# MAGHUG.net
KiCad netlist of a schematic drawn in EAGLE
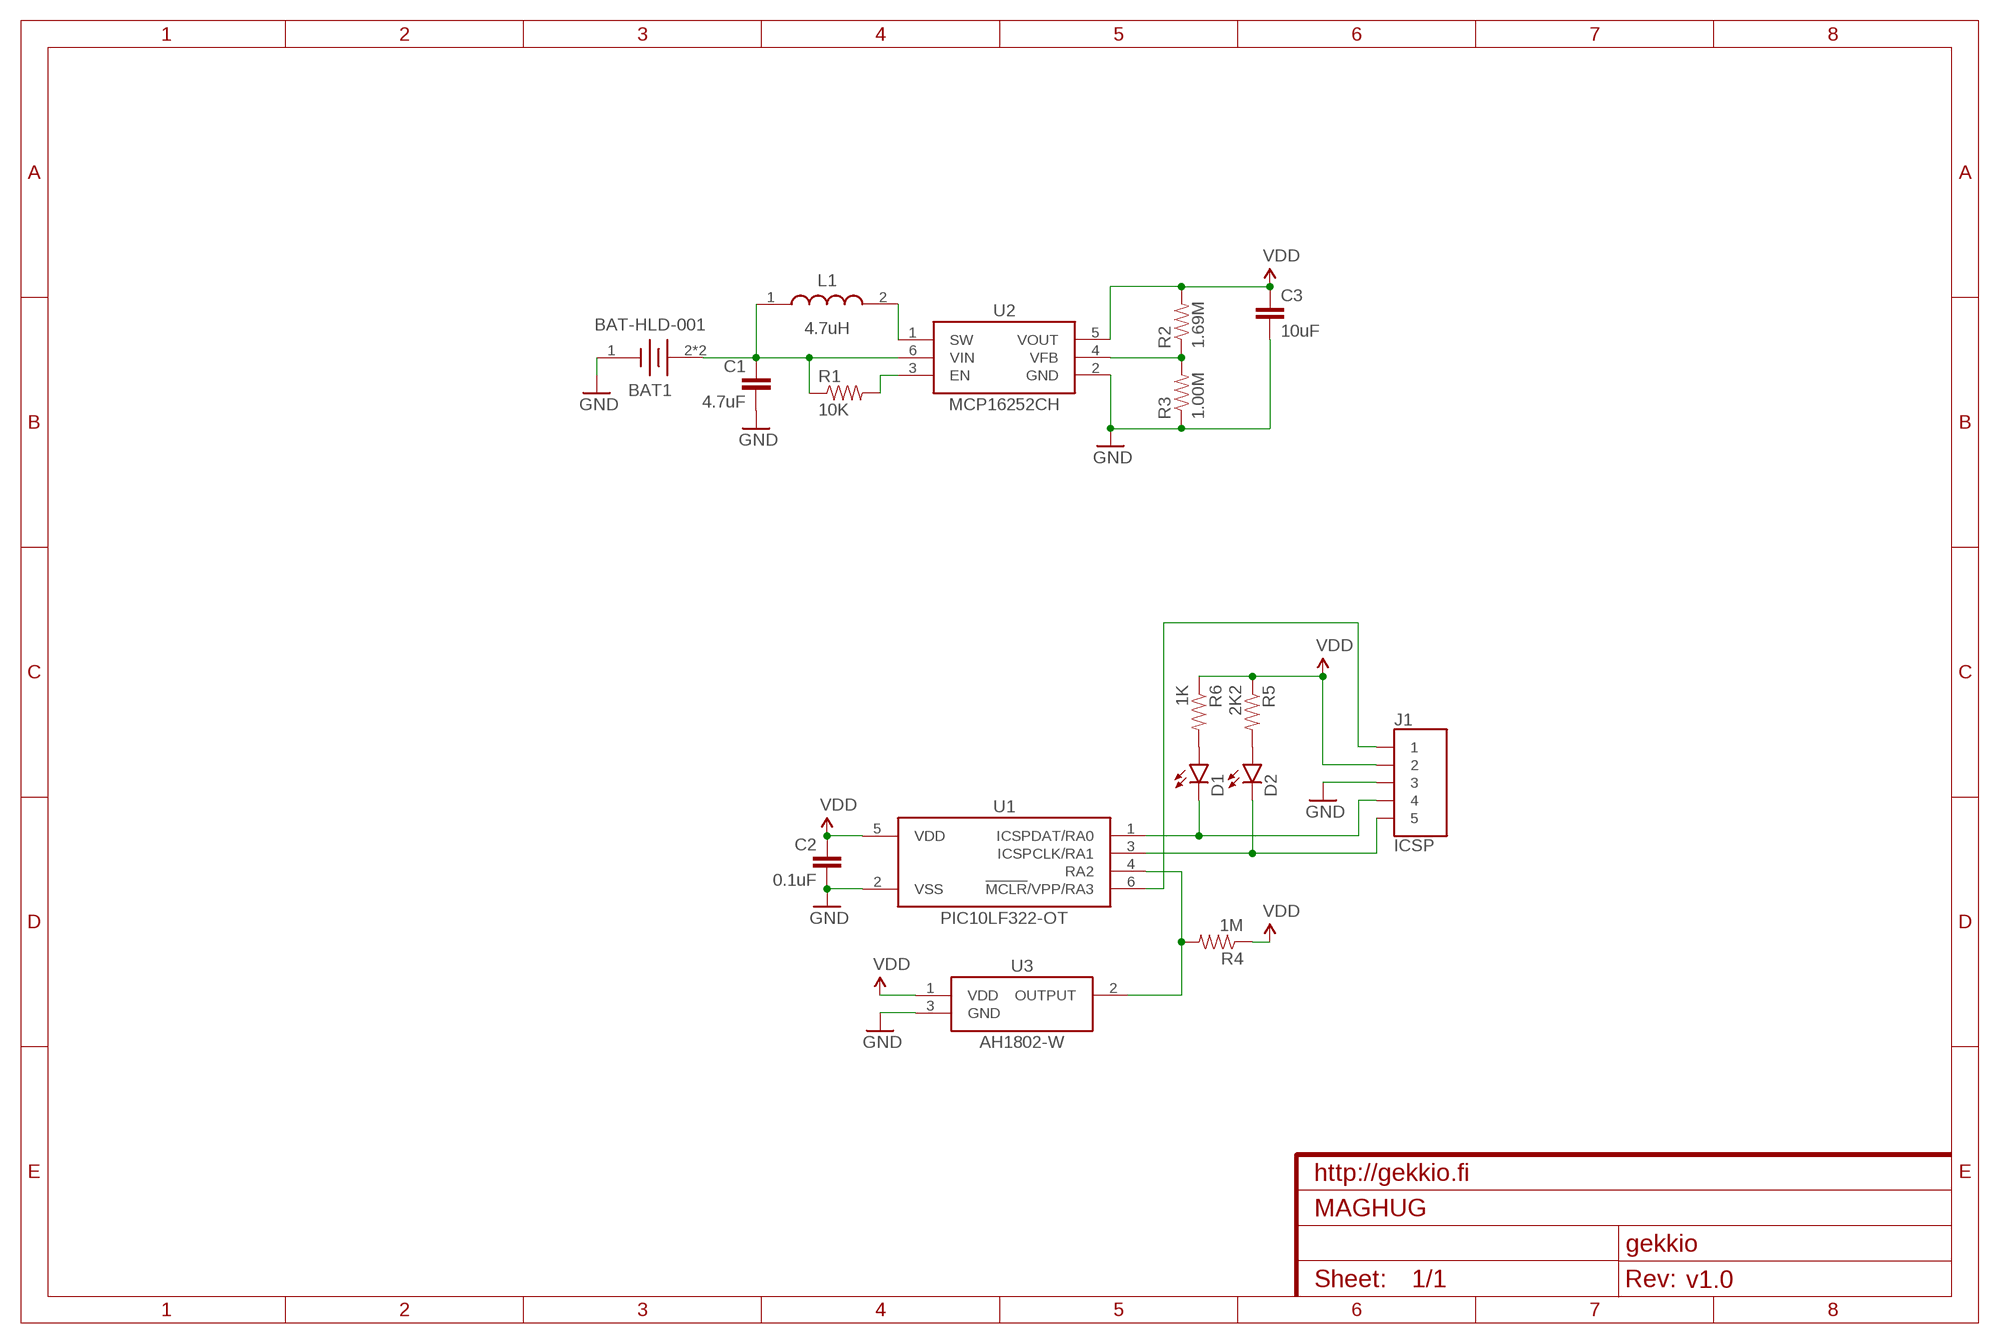
[diagram p0: schematic, sheet 1]

(export (version "E")
  (design (tool "Eeschema 10.0.6"))
  (components
    (comp (ref "BAT1")
      (value "BAT-HLD-001")
      (footprint "eagle-import:BAT-HLD-001")
      (libsource (lib "eagle-import") (part "BAT-HLD-001"))
    )
    (comp (ref "C1")
      (value "4.7uF")
      (footprint "eagle-import:0805")
      (libsource (lib "eagle-import") (part "CAP0805"))
    )
    (comp (ref "C2")
      (value "0.1uF")
      (footprint "eagle-import:0603-CAP")
      (libsource (lib "eagle-import") (part "CAP0603-CAP"))
    )
    (comp (ref "C3")
      (value "10uF")
      (footprint "eagle-import:0805")
      (libsource (lib "eagle-import") (part "CAP0805"))
    )
    (comp (ref "D1")
      (value "LED-3MM-NO_SILK")
      (footprint "eagle-import:LED3MM-NS")
      (libsource (lib "eagle-import") (part "LED-3MM-NO_SILK"))
    )
    (comp (ref "D2")
      (value "LED-3MM-NO_SILK")
      (footprint "eagle-import:LED3MM-NS")
      (libsource (lib "eagle-import") (part "LED-3MM-NO_SILK"))
    )
    (comp (ref "J1")
      (value "ICSP")
      (footprint "eagle-import:1X5-LONGPADS")
      (libsource (lib "eagle-import") (part "PINHD-1X5LONGPADS"))
    )
    (comp (ref "L1")
      (value "4.7uH")
      (footprint "eagle-import:VLS3015E")
      (libsource (lib "eagle-import") (part "VLS3015E"))
    )
    (comp (ref "R1")
      (value "10K")
      (footprint "eagle-import:0603-RES")
      (libsource (lib "eagle-import") (part "RESISTOR0603-RES"))
    )
    (comp (ref "R2")
      (value "1.69M")
      (footprint "eagle-import:0603-RES")
      (libsource (lib "eagle-import") (part "RESISTOR0603-RES"))
    )
    (comp (ref "R3")
      (value "1.00M")
      (footprint "eagle-import:0603-RES")
      (libsource (lib "eagle-import") (part "RESISTOR0603-RES"))
    )
    (comp (ref "R4")
      (value "1M")
      (footprint "eagle-import:0603-RES")
      (libsource (lib "eagle-import") (part "RESISTOR0603-RES"))
    )
    (comp (ref "R5")
      (value "2K2")
      (footprint "eagle-import:0603-RES")
      (libsource (lib "eagle-import") (part "RESISTOR0603-RES"))
    )
    (comp (ref "R6")
      (value "1K")
      (footprint "eagle-import:0603-RES")
      (libsource (lib "eagle-import") (part "RESISTOR0603-RES"))
    )
    (comp (ref "U1")
      (value "PIC10LF322-OT")
      (footprint "eagle-import:SOT-23(CH_CHY_OT)")
      (libsource (lib "eagle-import") (part "PIC10(L)F320/322-?OT"))
    )
    (comp (ref "U2")
      (value "MCP16252CH")
      (footprint "eagle-import:SOT-23(CH_CHY_OT)")
      (libsource (lib "eagle-import") (part "MCP16251/2(6PIN)CH"))
    )
    (comp (ref "U3")
      (value "AH1802-W")
      (footprint "eagle-import:SC59")
      (libsource (lib "eagle-import") (part "AH1802-?W"))
    )
  )
  (nets
    (net (code "1") (name "GND") (class "Default")
      (node (ref "BAT1") (pin "1") (pinfunction "-_1") (pintype "power_in"))
      (node (ref "C1") (pin "2") (pinfunction "2_2") (pintype "passive"))
      (node (ref "C2") (pin "2") (pinfunction "2_2") (pintype "passive"))
      (node (ref "C3") (pin "2") (pinfunction "2_2") (pintype "passive"))
      (node (ref "J1") (pin "3") (pinfunction "3_3") (pintype "passive"))
      (node (ref "R3") (pin "1") (pinfunction "1_1") (pintype "passive"))
      (node (ref "U1") (pin "2") (pinfunction "VSS_2") (pintype "power_in"))
      (node (ref "U2") (pin "2") (pinfunction "GND_2") (pintype "power_in"))
      (node (ref "U3") (pin "3") (pinfunction "GND_3") (pintype "power_in"))
    )
    (net (code "2") (name "Net-(D1-C)") (class "Default")
      (node (ref "D1") (pin "K") (pinfunction "C_K") (pintype "passive"))
      (node (ref "J1") (pin "4") (pinfunction "4_4") (pintype "passive"))
      (node (ref "U1") (pin "1") (pinfunction "ICSPDAT/RA0_1") (pintype "bidirectional"))
    )
    (net (code "3") (name "Net-(D1-PadA)") (class "Default")
      (node (ref "D1") (pin "A") (pinfunction "A_A") (pintype "passive"))
      (node (ref "R6") (pin "2") (pinfunction "2_2") (pintype "passive"))
    )
    (net (code "4") (name "Net-(D2-C)") (class "Default")
      (node (ref "D2") (pin "K") (pinfunction "C_K") (pintype "passive"))
      (node (ref "J1") (pin "5") (pinfunction "5_5") (pintype "passive"))
      (node (ref "U1") (pin "3") (pinfunction "ICSPCLK/RA1_3") (pintype "bidirectional"))
    )
    (net (code "5") (name "Net-(D2-PadA)") (class "Default")
      (node (ref "D2") (pin "A") (pinfunction "A_A") (pintype "passive"))
      (node (ref "R5") (pin "2") (pinfunction "2_2") (pintype "passive"))
    )
    (net (code "6") (name "Net-(U1-RA2)") (class "Default")
      (node (ref "R4") (pin "2") (pinfunction "2_2") (pintype "passive"))
      (node (ref "U1") (pin "4") (pinfunction "RA2_4") (pintype "bidirectional"))
      (node (ref "U3") (pin "2") (pinfunction "OUTPUT_2") (pintype "open_collector"))
    )
    (net (code "7") (name "Net-(U1-~{MCLR}{slash}VPP{slash}RA3)") (class "Default")
      (node (ref "J1") (pin "1") (pinfunction "1_1") (pintype "passive"))
      (node (ref "U1") (pin "6") (pinfunction "~{MCLR}/VPP/RA3_6") (pintype "bidirectional"))
    )
    (net (code "8") (name "Net-(U2-EN)") (class "Default")
      (node (ref "R1") (pin "2") (pinfunction "2_2") (pintype "passive"))
      (node (ref "U2") (pin "3") (pinfunction "EN_3") (pintype "input"))
    )
    (net (code "9") (name "Net-(U2-SW)") (class "Default")
      (node (ref "L1") (pin "2") (pinfunction "2_2") (pintype "passive"))
      (node (ref "U2") (pin "1") (pinfunction "SW_1") (pintype "passive"))
    )
    (net (code "10") (name "Net-(U2-VFB)") (class "Default")
      (node (ref "R2") (pin "1") (pinfunction "1_1") (pintype "passive"))
      (node (ref "R3") (pin "2") (pinfunction "2_2") (pintype "passive"))
      (node (ref "U2") (pin "4") (pinfunction "VFB_4") (pintype "passive"))
    )
    (net (code "11") (name "Net-(U2-VIN)") (class "Default")
      (node (ref "BAT1") (pin "2") (pinfunction "+_2") (pintype "power_in"))
      (node (ref "BAT1") (pin "3") (pinfunction "+_3") (pintype "power_in"))
      (node (ref "C1") (pin "1") (pinfunction "1_1") (pintype "passive"))
      (node (ref "L1") (pin "1") (pinfunction "1_1") (pintype "passive"))
      (node (ref "R1") (pin "1") (pinfunction "1_1") (pintype "passive"))
      (node (ref "U2") (pin "6") (pinfunction "VIN_6") (pintype "power_in"))
    )
    (net (code "12") (name "VDD") (class "Default")
      (node (ref "C2") (pin "1") (pinfunction "1_1") (pintype "passive"))
      (node (ref "C3") (pin "1") (pinfunction "1_1") (pintype "passive"))
      (node (ref "J1") (pin "2") (pinfunction "2_2") (pintype "passive"))
      (node (ref "R2") (pin "2") (pinfunction "2_2") (pintype "passive"))
      (node (ref "R4") (pin "1") (pinfunction "1_1") (pintype "passive"))
      (node (ref "R5") (pin "1") (pinfunction "1_1") (pintype "passive"))
      (node (ref "R6") (pin "1") (pinfunction "1_1") (pintype "passive"))
      (node (ref "U1") (pin "5") (pinfunction "VDD_5") (pintype "power_in"))
      (node (ref "U2") (pin "5") (pinfunction "VOUT_5") (pintype "power_in"))
      (node (ref "U3") (pin "1") (pinfunction "VDD_1") (pintype "power_in"))
    )
  )
)
